# schematic.net
KiCad netlist of a schematic drawn in Altium Designer
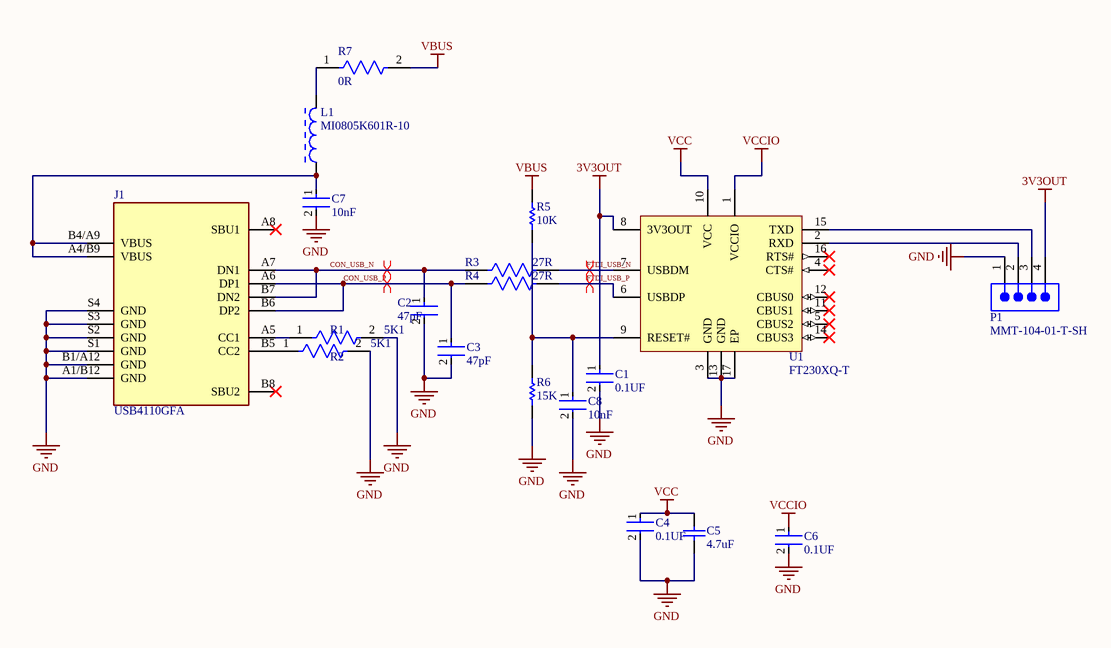
[diagram p0: schematic.SchDoc]

(export (version "E")
  (design (tool "Eeschema 10.0.6"))
  (components
    (comp (ref "C1")
      (value "0.1UF")
      (footprint "FP-C0402-BB-MFG")
      (description "CAP CER 0.1UF 25V X5R 0402")
      (fields
        (field (name "TOLERANCE") "0.2")
        (field (name "OCTOPART") "https://octopart.com/c0402c104m3pac7867-kemet-84304880")
      )
      (libsource (lib "Altium Content Vault") (part "b4654b650e69147ec39a6b967a45e02"))
    )
    (comp (ref "C2")
      (value "47pF")
      (footprint "FP-C0402-BB-MFG")
      (description "Cap Ceramic 47pF 25V X7R 5% Pad SMD 0402 125C Automotive T/R")
      (fields
        (field (name "OCTOPART") "https://octopart.com/c0402c470j3racauto-kemet-86584164")
        (field (name "MANUFACTURER") "Kemet")
      )
      (libsource (lib "Altium Content Vault") (part "b4654b650e69147ec39a6b967a45e02"))
    )
    (comp (ref "C3")
      (value "47pF")
      (footprint "FP-C0402-BB-MFG")
      (description "Cap Ceramic 47pF 25V X7R 5% Pad SMD 0402 125C Automotive T/R")
      (fields
        (field (name "OCTOPART") "https://octopart.com/c0402c470j3racauto-kemet-86584164")
        (field (name "MANUFACTURER") "Kemet")
      )
      (libsource (lib "Altium Content Vault") (part "b4654b650e69147ec39a6b967a45e02"))
    )
    (comp (ref "C4")
      (value "0.1UF")
      (footprint "FP-C0402-BB-MFG")
      (description "CAP CER 0.1UF 25V X5R 0402")
      (fields
        (field (name "TOLERANCE") "0.2")
        (field (name "OCTOPART") "https://octopart.com/c0402c104m3pac7867-kemet-84304880")
      )
      (libsource (lib "Altium Content Vault") (part "b4654b650e69147ec39a6b967a45e02"))
    )
    (comp (ref "C5")
      (value "4.7uF")
      (footprint "CAPC2013X145X50ML20T25")
      (fields (field (name "MANUFACTURER") "Kemet") (field (name "PART NUMBER") "C0805C475M4PACTU"))
      (libsource (lib "Altium Content Vault") (part "CAP"))
    )
    (comp (ref "C6")
      (value "0.1UF")
      (footprint "FP-C0402-BB-MFG")
      (description "CAP CER 0.1UF 25V X5R 0402")
      (fields
        (field (name "TOLERANCE") "0.2")
        (field (name "OCTOPART") "https://octopart.com/c0402c104m3pac7867-kemet-84304880")
      )
      (libsource (lib "Altium Content Vault") (part "b4654b650e69147ec39a6b967a45e02"))
    )
    (comp (ref "C7")
      (value "10nF")
      (footprint "FP-C0402-BB-MFG")
      (description "C0402 10,000 pF X7R 10.00% 50 V")
      (fields
        (field (name "OCTOPART") "https://octopart.com/c0402c103k5rac-kemet-7501684")
        (field (name "MANUFACTURER PART NUMBER") "C0402C103K5RAC")
      )
      (libsource (lib "Altium Content Vault") (part "b4654b650e69147ec39a6b967a45e02"))
    )
    (comp (ref "C8")
      (value "10nF")
      (footprint "FP-C0402-BB-MFG")
      (description "C0402 10,000 pF X7R 10.00% 50 V")
      (fields
        (field (name "OCTOPART") "https://octopart.com/c0402c103k5rac-kemet-7501684")
        (field (name "MANUFACTURER PART NUMBER") "C0402C103K5RAC")
      )
      (libsource (lib "Altium Content Vault") (part "b4654b650e69147ec39a6b967a45e02"))
    )
    (comp (ref "J1")
      (value "USB4110GFA")
      (footprint "GCT_USB4110GFA")
      (fields (field (name "MF") "Global Connector Technology"))
      (libsource (lib "USB-C") (part "USB4110GFA"))
    )
    (comp (ref "L1")
      (value "MI0805K601R-10")
      (footprint "LIRD-MI0805K601R-10-2_V")
      (fields (field (name "MANUFACTURER") "Laird"))
      (libsource (lib "Altium Content Vault") (part "IND-FB-2"))
    )
    (comp (ref "P1")
      (value "MMT-104-01-T-SH")
      (footprint "SMTC-MMT-104-01-X-SH")
      (description "Horizontal Surface Mount Header, -55 to 105 degC, 2 mm Pitch, 4-Pin, Male, RoHS")
      (fields (field (name "MANUFACTURER") "Samtec"))
      (libsource (lib "Altium Content Vault") (part "SMTC-MMT-104-X-X-SH"))
    )
    (comp (ref "R1")
      (value "5K1")
      (footprint "FP-CRCW0402-e3-IPC_A")
      (description "RES Thick Film, 5.1kΩ, 5%, 0.063W, 200ppm/°C, 0402")
      (fields (field (name "TOLERANCE") "5%"))
      (libsource (lib "") (part "1029c3af85768c4190bb7ad29bc67b5_1"))
    )
    (comp (ref "R2")
      (value "5K1")
      (footprint "FP-CRCW0402-e3-IPC_A")
      (description "RES Thick Film, 5.1kΩ, 5%, 0.063W, 200ppm/°C, 0402")
      (fields (field (name "TOLERANCE") "5%"))
      (libsource (lib "") (part "1029c3af85768c4190bb7ad29bc67b5_1"))
    )
    (comp (ref "R3")
      (value "27R")
      (footprint "FP-AC0402-MFG")
      (description "RES 27Ω ±5% 0.063W 0402")
      (fields (field (name "TOLERANCE") "5%"))
      (libsource (lib "Altium Content Vault") (part "1029c3af85768c4190bb7ad29bc67b5"))
    )
    (comp (ref "R4")
      (value "27R")
      (footprint "FP-AC0402-MFG")
      (description "RES 27Ω ±5% 0.063W 0402")
      (fields (field (name "TOLERANCE") "5%"))
      (libsource (lib "Altium Content Vault") (part "1029c3af85768c4190bb7ad29bc67b5"))
    )
    (comp (ref "R5")
      (value "10K")
      (footprint "RESC1005X40X20NL05T10")
      (fields
        (field (name "MANUFACTURER") "Vishay BCcomponents")
        (field (name "PART NUMBER") "TNPW040210K0DEED")
      )
      (libsource (lib "Altium Content Vault") (part "RES"))
    )
    (comp (ref "R6")
      (value "15K")
      (footprint "RESC1005X40X20NL05T10")
      (fields
        (field (name "MANUFACTURER") "Vishay BCcomponents")
        (field (name "PART NUMBER") "TNPW040210K0DEED")
      )
      (libsource (lib "Altium Content Vault") (part "RES"))
    )
    (comp (ref "R7")
      (value "0R")
      (footprint "FP-AF1206-MFG")
      (description "Anti-Sulfurated Chip Resistor Automotive Grade 0Ω Jumper 0.25W 1206")
      (fields (field (name "TOLERANCE") "5%"))
      (libsource (lib "") (part "1029c3af85768c4190bb7ad29bc67b5_1"))
    )
    (comp (ref "U1")
      (value "FT230XQ-T")
      (footprint "QFN-16_M")
      (fields (field (name "MANUFACTURER") "FTDI"))
      (libsource (lib "Altium Content Vault") (part "COM-USB-FT230XQ-SQ17"))
    )
  )
  (nets
    (net (code "1") (name "/CON_USB_N") (class "Default")
      (node (ref "C2") (pin "1") (pinfunction "1_1") (pintype "passive"))
      (node (ref "J1") (pin "A7") (pinfunction "DN1_A7") (pintype "passive"))
      (node (ref "J1") (pin "B7") (pinfunction "DN2_B7") (pintype "passive"))
      (node (ref "R3") (pin "1") (pinfunction "1_1") (pintype "passive"))
    )
    (net (code "2") (name "/CON_USB_P") (class "Default")
      (node (ref "C3") (pin "1") (pinfunction "1_1") (pintype "passive"))
      (node (ref "J1") (pin "A6") (pinfunction "DP1_A6") (pintype "passive"))
      (node (ref "J1") (pin "B6") (pinfunction "DP2_B6") (pintype "passive"))
      (node (ref "R4") (pin "1") (pinfunction "1_1") (pintype "passive"))
    )
    (net (code "3") (name "/FTDI_USB_N") (class "Default")
      (node (ref "R3") (pin "2") (pinfunction "2_2") (pintype "passive"))
      (node (ref "U1") (pin "7") (pinfunction "USBDM_7") (pintype "passive"))
    )
    (net (code "4") (name "/FTDI_USB_P") (class "Default")
      (node (ref "R4") (pin "2") (pinfunction "2_2") (pintype "passive"))
      (node (ref "U1") (pin "6") (pinfunction "USBDP_6") (pintype "passive"))
    )
    (net (code "5") (name "3V3OUT") (class "Default")
      (node (ref "C1") (pin "1") (pinfunction "1_1") (pintype "passive"))
      (node (ref "P1") (pin "4") (pinfunction "4_4") (pintype "passive"))
      (node (ref "U1") (pin "8") (pinfunction "3V3OUT_8") (pintype "power_in"))
    )
    (net (code "6") (name "GND") (class "Default")
      (node (ref "C1") (pin "2") (pinfunction "2_2") (pintype "passive"))
      (node (ref "C2") (pin "2") (pinfunction "2_2") (pintype "passive"))
      (node (ref "C3") (pin "2") (pinfunction "2_2") (pintype "passive"))
      (node (ref "C4") (pin "2") (pinfunction "2_2") (pintype "passive"))
      (node (ref "C5") (pin "1") (pinfunction "1_1") (pintype "passive"))
      (node (ref "C6") (pin "2") (pinfunction "2_2") (pintype "passive"))
      (node (ref "C7") (pin "2") (pinfunction "2_2") (pintype "passive"))
      (node (ref "C8") (pin "2") (pinfunction "2_2") (pintype "passive"))
      (node (ref "J1") (pin "A1/B12") (pinfunction "GND_A1/B12") (pintype "passive"))
      (node (ref "J1") (pin "B1/A12") (pinfunction "GND_B1/A12") (pintype "passive"))
      (node (ref "J1") (pin "S1") (pinfunction "GND_S1") (pintype "passive"))
      (node (ref "J1") (pin "S2") (pinfunction "GND_S2") (pintype "passive"))
      (node (ref "J1") (pin "S3") (pinfunction "GND_S3") (pintype "passive"))
      (node (ref "J1") (pin "S4") (pinfunction "GND_S4") (pintype "passive"))
      (node (ref "P1") (pin "1") (pinfunction "1_1") (pintype "passive"))
      (node (ref "R1") (pin "2") (pinfunction "2_2") (pintype "passive"))
      (node (ref "R2") (pin "2") (pinfunction "2_2") (pintype "passive"))
      (node (ref "R6") (pin "2") (pinfunction "2_2") (pintype "passive"))
      (node (ref "U1") (pin "13") (pinfunction "GND_13") (pintype "power_in"))
      (node (ref "U1") (pin "17") (pinfunction "EP_17") (pintype "power_in"))
      (node (ref "U1") (pin "3") (pinfunction "GND_3") (pintype "power_in"))
    )
    (net (code "7") (name "Net-(C7-Pad1)") (class "Default")
      (node (ref "C7") (pin "1") (pinfunction "1_1") (pintype "passive"))
      (node (ref "J1") (pin "A4/B9") (pinfunction "VBUS_A4/B9") (pintype "passive"))
      (node (ref "J1") (pin "B4/A9") (pinfunction "VBUS_B4/A9") (pintype "passive"))
      (node (ref "L1") (pin "1") (pinfunction "1_1") (pintype "passive"))
    )
    (net (code "8") (name "Net-(J1-CC1)") (class "Default")
      (node (ref "J1") (pin "A5") (pinfunction "CC1_A5") (pintype "passive"))
      (node (ref "R1") (pin "1") (pinfunction "1_1") (pintype "passive"))
    )
    (net (code "9") (name "Net-(J1-CC2)") (class "Default")
      (node (ref "J1") (pin "B5") (pinfunction "CC2_B5") (pintype "passive"))
      (node (ref "R2") (pin "1") (pinfunction "1_1") (pintype "passive"))
    )
    (net (code "10") (name "Net-(L1-Pad2)") (class "Default")
      (node (ref "L1") (pin "2") (pinfunction "2_2") (pintype "passive"))
      (node (ref "R7") (pin "1") (pinfunction "1_1") (pintype "passive"))
    )
    (net (code "11") (name "Net-(U1-RESET#)") (class "Default")
      (node (ref "C8") (pin "1") (pinfunction "1_1") (pintype "passive"))
      (node (ref "R5") (pin "2") (pinfunction "2_2") (pintype "passive"))
      (node (ref "R6") (pin "1") (pinfunction "1_1") (pintype "passive"))
      (node (ref "U1") (pin "9") (pinfunction "RESET#_9") (pintype "passive"))
    )
    (net (code "12") (name "Net-(U1-RXD)") (class "Default")
      (node (ref "P1") (pin "2") (pinfunction "2_2") (pintype "passive"))
      (node (ref "U1") (pin "2") (pinfunction "RXD_2") (pintype "passive"))
    )
    (net (code "13") (name "Net-(U1-TXD)") (class "Default")
      (node (ref "P1") (pin "3") (pinfunction "3_3") (pintype "passive"))
      (node (ref "U1") (pin "15") (pinfunction "TXD_15") (pintype "passive"))
    )
    (net (code "14") (name "VBUS") (class "Default")
      (node (ref "R5") (pin "1") (pinfunction "1_1") (pintype "passive"))
      (node (ref "R7") (pin "2") (pinfunction "2_2") (pintype "passive"))
    )
    (net (code "15") (name "VCC") (class "Default")
      (node (ref "C4") (pin "1") (pinfunction "1_1") (pintype "passive"))
      (node (ref "C5") (pin "2") (pinfunction "2_2") (pintype "passive"))
      (node (ref "U1") (pin "10") (pinfunction "VCC_10") (pintype "power_in"))
    )
    (net (code "16") (name "VCCIO") (class "Default")
      (node (ref "C6") (pin "1") (pinfunction "1_1") (pintype "passive"))
      (node (ref "U1") (pin "1") (pinfunction "VCCIO_1") (pintype "power_in"))
    )
    (net (code "17") (name "unconnected-(J1-SBU1-PadA8)") (class "Default")
      (node (ref "J1") (pin "A8") (pinfunction "SBU1_A8") (pintype "passive+no_connect"))
    )
    (net (code "18") (name "unconnected-(J1-SBU2-PadB8)") (class "Default")
      (node (ref "J1") (pin "B8") (pinfunction "SBU2_B8") (pintype "passive+no_connect"))
    )
    (net (code "19") (name "unconnected-(U1-CBUS0-Pad12)") (class "Default")
      (node (ref "U1") (pin "12") (pinfunction "CBUS0_12") (pintype "bidirectional+no_connect"))
    )
    (net (code "20") (name "unconnected-(U1-CBUS1-Pad11)") (class "Default")
      (node (ref "U1") (pin "11") (pinfunction "CBUS1_11") (pintype "bidirectional+no_connect"))
    )
    (net (code "21") (name "unconnected-(U1-CBUS2-Pad5)") (class "Default")
      (node (ref "U1") (pin "5") (pinfunction "CBUS2_5") (pintype "bidirectional+no_connect"))
    )
    (net (code "22") (name "unconnected-(U1-CBUS3-Pad14)") (class "Default")
      (node (ref "U1") (pin "14") (pinfunction "CBUS3_14") (pintype "bidirectional+no_connect"))
    )
    (net (code "23") (name "unconnected-(U1-CTS#-Pad4)") (class "Default")
      (node (ref "U1") (pin "4") (pinfunction "CTS#_4") (pintype "input+no_connect"))
    )
    (net (code "24") (name "unconnected-(U1-RTS#-Pad16)") (class "Default")
      (node (ref "U1") (pin "16") (pinfunction "RTS#_16") (pintype "output+no_connect"))
    )
  )
)
